# 04_-_Current_Transformers.net
KiCad netlist of a schematic drawn in Altium Designer
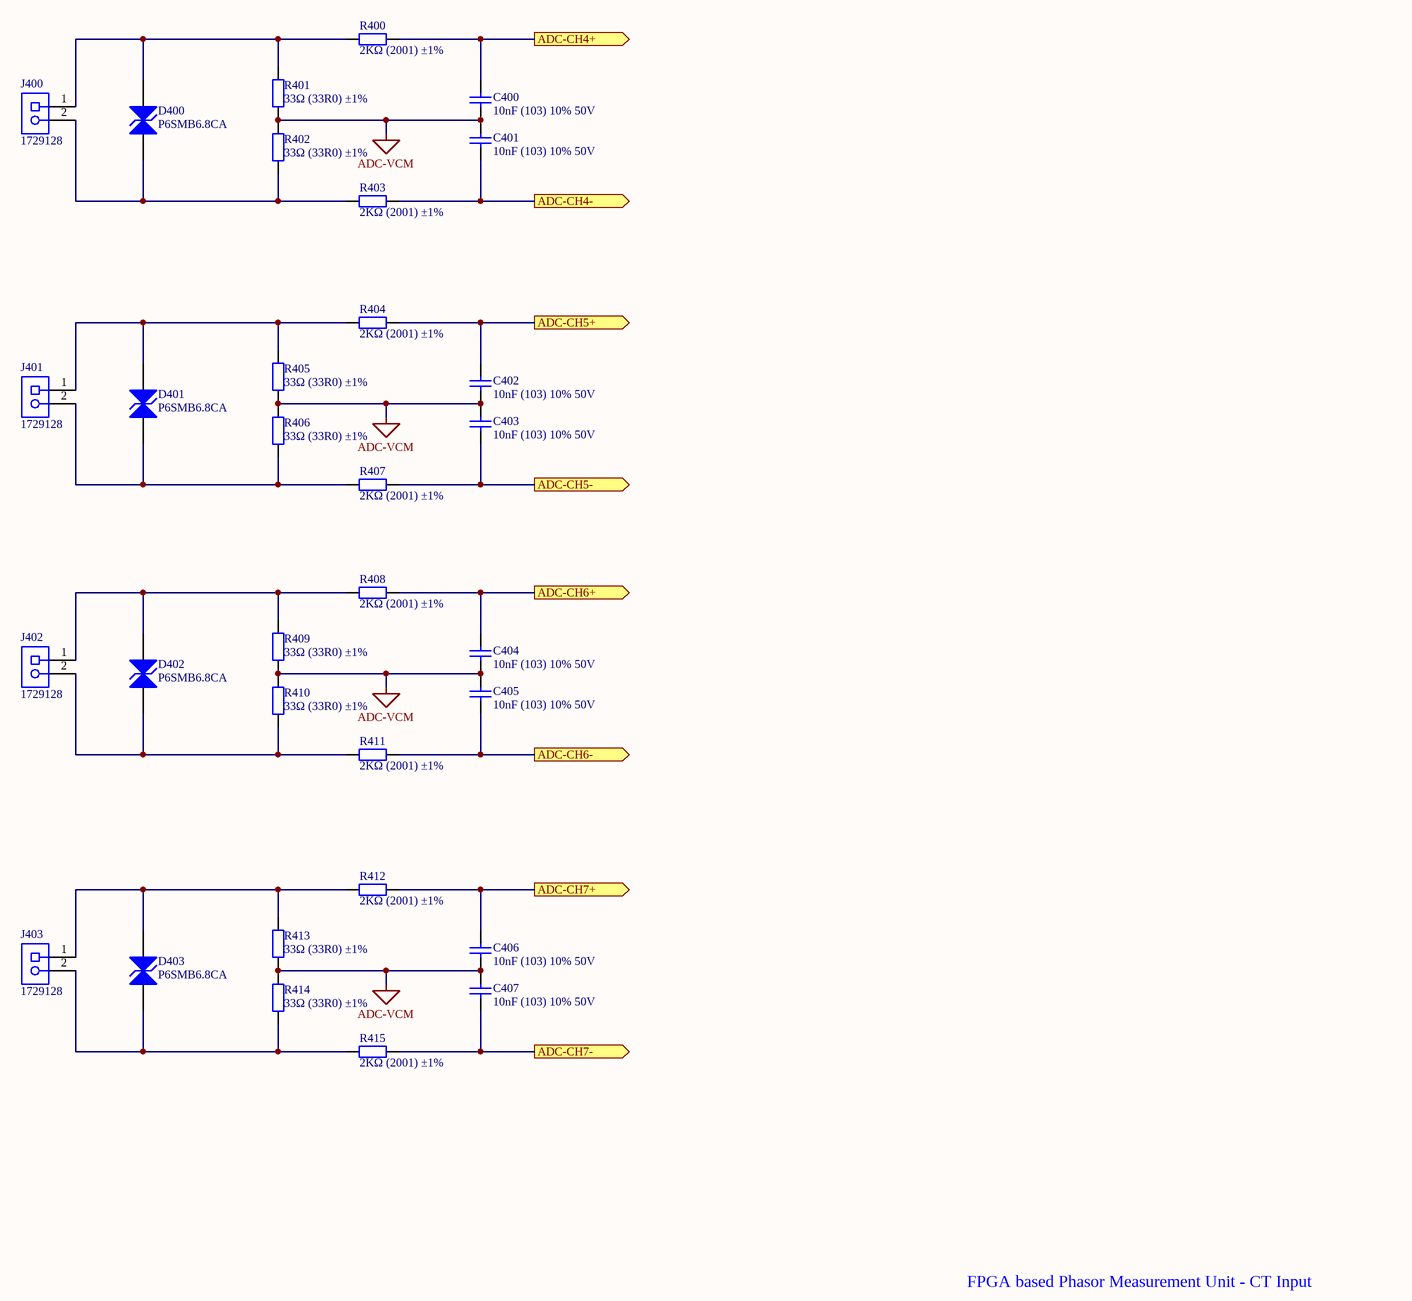
[diagram p0: [04] - Current Transformers.SchDoc]

(export (version "E")
  (design (tool "Eeschema 10.0.6"))
  (components
    (comp (ref "C400")
      (value "10nF (103) 10% 50V")
      (footprint "0805_C")
      (description "贴片电容")
      (libsource (lib "Cap") (part "0805 10nF (103) 10% 50V"))
    )
    (comp (ref "C401")
      (value "10nF (103) 10% 50V")
      (footprint "0805_C")
      (description "贴片电容")
      (libsource (lib "Cap") (part "0805 10nF (103) 10% 50V"))
    )
    (comp (ref "C402")
      (value "10nF (103) 10% 50V")
      (footprint "0805_C")
      (description "贴片电容")
      (libsource (lib "Cap") (part "0805 10nF (103) 10% 50V"))
    )
    (comp (ref "C403")
      (value "10nF (103) 10% 50V")
      (footprint "0805_C")
      (description "贴片电容")
      (libsource (lib "Cap") (part "0805 10nF (103) 10% 50V"))
    )
    (comp (ref "C404")
      (value "10nF (103) 10% 50V")
      (footprint "0805_C")
      (description "贴片电容")
      (libsource (lib "Cap") (part "0805 10nF (103) 10% 50V"))
    )
    (comp (ref "C405")
      (value "10nF (103) 10% 50V")
      (footprint "0805_C")
      (description "贴片电容")
      (libsource (lib "Cap") (part "0805 10nF (103) 10% 50V"))
    )
    (comp (ref "C406")
      (value "10nF (103) 10% 50V")
      (footprint "0805_C")
      (description "贴片电容")
      (libsource (lib "Cap") (part "0805 10nF (103) 10% 50V"))
    )
    (comp (ref "C407")
      (value "10nF (103) 10% 50V")
      (footprint "0805_C")
      (description "贴片电容")
      (libsource (lib "Cap") (part "0805 10nF (103) 10% 50V"))
    )
    (comp (ref "D400")
      (value "P6SMB6.8CA")
      (footprint "SMB(DO-214AA)_S1")
      (description "TVS")
      (libsource (lib "Diode") (part "SMB/DO-214AA P6SMB6.8CA"))
    )
    (comp (ref "D401")
      (value "P6SMB6.8CA")
      (footprint "SMB(DO-214AA)_S1")
      (description "TVS")
      (libsource (lib "Diode") (part "SMB/DO-214AA P6SMB6.8CA"))
    )
    (comp (ref "D402")
      (value "P6SMB6.8CA")
      (footprint "SMB(DO-214AA)_S1")
      (description "TVS")
      (libsource (lib "Diode") (part "SMB/DO-214AA P6SMB6.8CA"))
    )
    (comp (ref "D403")
      (value "P6SMB6.8CA")
      (footprint "SMB(DO-214AA)_S1")
      (description "TVS")
      (libsource (lib "Diode") (part "SMB/DO-214AA P6SMB6.8CA"))
    )
    (comp (ref "J400")
      (value "1729128")
      (footprint "PHOE-1729128-2_V")
      (description "PCB Terminal Block, 13.5 A, 400 V, 2-Pin THD, RoHS, Bulk")
      (fields (field (name "MANUFACTURER") "Phoenix Contact"))
      (libsource (lib "Altium Content Vault") (part "CN-2P-F-R2"))
    )
    (comp (ref "J401")
      (value "1729128")
      (footprint "PHOE-1729128-2_V")
      (description "PCB Terminal Block, 13.5 A, 400 V, 2-Pin THD, RoHS, Bulk")
      (fields (field (name "MANUFACTURER") "Phoenix Contact"))
      (libsource (lib "Altium Content Vault") (part "CN-2P-F-R2"))
    )
    (comp (ref "J402")
      (value "1729128")
      (footprint "PHOE-1729128-2_V")
      (description "PCB Terminal Block, 13.5 A, 400 V, 2-Pin THD, RoHS, Bulk")
      (fields (field (name "MANUFACTURER") "Phoenix Contact"))
      (libsource (lib "Altium Content Vault") (part "CN-2P-F-R2"))
    )
    (comp (ref "J403")
      (value "1729128")
      (footprint "PHOE-1729128-2_V")
      (description "PCB Terminal Block, 13.5 A, 400 V, 2-Pin THD, RoHS, Bulk")
      (fields (field (name "MANUFACTURER") "Phoenix Contact"))
      (libsource (lib "Altium Content Vault") (part "CN-2P-F-R2"))
    )
    (comp (ref "R400")
      (value "2KΩ (2001) ±1%")
      (footprint "0805_R")
      (description "贴片电阻")
      (libsource (lib "RES") (part "0805 2KΩ (2001) 1%"))
    )
    (comp (ref "R401")
      (value "33Ω (33R0) ±1%")
      (footprint "0603_R")
      (description "贴片电阻")
      (libsource (lib "RES") (part "0603 33Ω (33R0) 1%"))
    )
    (comp (ref "R402")
      (value "33Ω (33R0) ±1%")
      (footprint "0603_R")
      (description "贴片电阻")
      (libsource (lib "RES") (part "0603 33Ω (33R0) 1%"))
    )
    (comp (ref "R403")
      (value "2KΩ (2001) ±1%")
      (footprint "0805_R")
      (description "贴片电阻")
      (libsource (lib "RES") (part "0805 2KΩ (2001) 1%"))
    )
    (comp (ref "R404")
      (value "2KΩ (2001) ±1%")
      (footprint "0805_R")
      (description "贴片电阻")
      (libsource (lib "RES") (part "0805 2KΩ (2001) 1%"))
    )
    (comp (ref "R405")
      (value "33Ω (33R0) ±1%")
      (footprint "0603_R")
      (description "贴片电阻")
      (libsource (lib "RES") (part "0603 33Ω (33R0) 1%"))
    )
    (comp (ref "R406")
      (value "33Ω (33R0) ±1%")
      (footprint "0603_R")
      (description "贴片电阻")
      (libsource (lib "RES") (part "0603 33Ω (33R0) 1%"))
    )
    (comp (ref "R407")
      (value "2KΩ (2001) ±1%")
      (footprint "0805_R")
      (description "贴片电阻")
      (libsource (lib "RES") (part "0805 2KΩ (2001) 1%"))
    )
    (comp (ref "R408")
      (value "2KΩ (2001) ±1%")
      (footprint "0805_R")
      (description "贴片电阻")
      (libsource (lib "RES") (part "0805 2KΩ (2001) 1%"))
    )
    (comp (ref "R409")
      (value "33Ω (33R0) ±1%")
      (footprint "0603_R")
      (description "贴片电阻")
      (libsource (lib "RES") (part "0603 33Ω (33R0) 1%"))
    )
    (comp (ref "R410")
      (value "33Ω (33R0) ±1%")
      (footprint "0603_R")
      (description "贴片电阻")
      (libsource (lib "RES") (part "0603 33Ω (33R0) 1%"))
    )
    (comp (ref "R411")
      (value "2KΩ (2001) ±1%")
      (footprint "0805_R")
      (description "贴片电阻")
      (libsource (lib "RES") (part "0805 2KΩ (2001) 1%"))
    )
    (comp (ref "R412")
      (value "2KΩ (2001) ±1%")
      (footprint "0805_R")
      (description "贴片电阻")
      (libsource (lib "RES") (part "0805 2KΩ (2001) 1%"))
    )
    (comp (ref "R413")
      (value "33Ω (33R0) ±1%")
      (footprint "0603_R")
      (description "贴片电阻")
      (libsource (lib "RES") (part "0603 33Ω (33R0) 1%"))
    )
    (comp (ref "R414")
      (value "33Ω (33R0) ±1%")
      (footprint "0603_R")
      (description "贴片电阻")
      (libsource (lib "RES") (part "0603 33Ω (33R0) 1%"))
    )
    (comp (ref "R415")
      (value "2KΩ (2001) ±1%")
      (footprint "0805_R")
      (description "贴片电阻")
      (libsource (lib "RES") (part "0805 2KΩ (2001) 1%"))
    )
  )
  (nets
    (net (code "1") (name "/ADC-CH4+") (class "Default")
      (node (ref "C400") (pin "2") (pinfunction "2_2") (pintype "passive"))
      (node (ref "R400") (pin "1") (pinfunction "1_1") (pintype "passive"))
    )
    (net (code "2") (name "/ADC-CH4-") (class "Default")
      (node (ref "C401") (pin "1") (pinfunction "1_1") (pintype "passive"))
      (node (ref "R403") (pin "1") (pinfunction "1_1") (pintype "passive"))
    )
    (net (code "3") (name "/ADC-CH5+") (class "Default")
      (node (ref "C402") (pin "2") (pinfunction "2_2") (pintype "passive"))
      (node (ref "R404") (pin "1") (pinfunction "1_1") (pintype "passive"))
    )
    (net (code "4") (name "/ADC-CH5-") (class "Default")
      (node (ref "C403") (pin "1") (pinfunction "1_1") (pintype "passive"))
      (node (ref "R407") (pin "1") (pinfunction "1_1") (pintype "passive"))
    )
    (net (code "5") (name "/ADC-CH6+") (class "Default")
      (node (ref "C404") (pin "2") (pinfunction "2_2") (pintype "passive"))
      (node (ref "R408") (pin "1") (pinfunction "1_1") (pintype "passive"))
    )
    (net (code "6") (name "/ADC-CH6-") (class "Default")
      (node (ref "C405") (pin "1") (pinfunction "1_1") (pintype "passive"))
      (node (ref "R411") (pin "1") (pinfunction "1_1") (pintype "passive"))
    )
    (net (code "7") (name "/ADC-CH7+") (class "Default")
      (node (ref "C406") (pin "2") (pinfunction "2_2") (pintype "passive"))
      (node (ref "R412") (pin "1") (pinfunction "1_1") (pintype "passive"))
    )
    (net (code "8") (name "/ADC-CH7-") (class "Default")
      (node (ref "C407") (pin "1") (pinfunction "1_1") (pintype "passive"))
      (node (ref "R415") (pin "1") (pinfunction "1_1") (pintype "passive"))
    )
    (net (code "9") (name "ADC-VCM") (class "Default")
      (node (ref "C400") (pin "1") (pinfunction "1_1") (pintype "passive"))
      (node (ref "C401") (pin "2") (pinfunction "2_2") (pintype "passive"))
      (node (ref "C402") (pin "1") (pinfunction "1_1") (pintype "passive"))
      (node (ref "C403") (pin "2") (pinfunction "2_2") (pintype "passive"))
      (node (ref "C404") (pin "1") (pinfunction "1_1") (pintype "passive"))
      (node (ref "C405") (pin "2") (pinfunction "2_2") (pintype "passive"))
      (node (ref "C406") (pin "1") (pinfunction "1_1") (pintype "passive"))
      (node (ref "C407") (pin "2") (pinfunction "2_2") (pintype "passive"))
      (node (ref "R401") (pin "1") (pinfunction "1_1") (pintype "passive"))
      (node (ref "R402") (pin "2") (pinfunction "2_2") (pintype "passive"))
      (node (ref "R405") (pin "1") (pinfunction "1_1") (pintype "passive"))
      (node (ref "R406") (pin "2") (pinfunction "2_2") (pintype "passive"))
      (node (ref "R409") (pin "1") (pinfunction "1_1") (pintype "passive"))
      (node (ref "R410") (pin "2") (pinfunction "2_2") (pintype "passive"))
      (node (ref "R413") (pin "1") (pinfunction "1_1") (pintype "passive"))
      (node (ref "R414") (pin "2") (pinfunction "2_2") (pintype "passive"))
    )
    (net (code "10") (name "Net-(D400-A)") (class "Default")
      (node (ref "D400") (pin "1") (pinfunction "A_1") (pintype "passive"))
      (node (ref "J400") (pin "2") (pinfunction "2_2") (pintype "passive"))
      (node (ref "R402") (pin "1") (pinfunction "1_1") (pintype "passive"))
      (node (ref "R403") (pin "2") (pinfunction "2_2") (pintype "passive"))
    )
    (net (code "11") (name "Net-(D400-K)") (class "Default")
      (node (ref "D400") (pin "2") (pinfunction "K_2") (pintype "passive"))
      (node (ref "J400") (pin "1") (pinfunction "1_1") (pintype "passive"))
      (node (ref "R400") (pin "2") (pinfunction "2_2") (pintype "passive"))
      (node (ref "R401") (pin "2") (pinfunction "2_2") (pintype "passive"))
    )
    (net (code "12") (name "Net-(D401-A)") (class "Default")
      (node (ref "D401") (pin "1") (pinfunction "A_1") (pintype "passive"))
      (node (ref "J401") (pin "2") (pinfunction "2_2") (pintype "passive"))
      (node (ref "R406") (pin "1") (pinfunction "1_1") (pintype "passive"))
      (node (ref "R407") (pin "2") (pinfunction "2_2") (pintype "passive"))
    )
    (net (code "13") (name "Net-(D401-K)") (class "Default")
      (node (ref "D401") (pin "2") (pinfunction "K_2") (pintype "passive"))
      (node (ref "J401") (pin "1") (pinfunction "1_1") (pintype "passive"))
      (node (ref "R404") (pin "2") (pinfunction "2_2") (pintype "passive"))
      (node (ref "R405") (pin "2") (pinfunction "2_2") (pintype "passive"))
    )
    (net (code "14") (name "Net-(D402-A)") (class "Default")
      (node (ref "D402") (pin "1") (pinfunction "A_1") (pintype "passive"))
      (node (ref "J402") (pin "2") (pinfunction "2_2") (pintype "passive"))
      (node (ref "R410") (pin "1") (pinfunction "1_1") (pintype "passive"))
      (node (ref "R411") (pin "2") (pinfunction "2_2") (pintype "passive"))
    )
    (net (code "15") (name "Net-(D402-K)") (class "Default")
      (node (ref "D402") (pin "2") (pinfunction "K_2") (pintype "passive"))
      (node (ref "J402") (pin "1") (pinfunction "1_1") (pintype "passive"))
      (node (ref "R408") (pin "2") (pinfunction "2_2") (pintype "passive"))
      (node (ref "R409") (pin "2") (pinfunction "2_2") (pintype "passive"))
    )
    (net (code "16") (name "Net-(D403-A)") (class "Default")
      (node (ref "D403") (pin "1") (pinfunction "A_1") (pintype "passive"))
      (node (ref "J403") (pin "2") (pinfunction "2_2") (pintype "passive"))
      (node (ref "R414") (pin "1") (pinfunction "1_1") (pintype "passive"))
      (node (ref "R415") (pin "2") (pinfunction "2_2") (pintype "passive"))
    )
    (net (code "17") (name "Net-(D403-K)") (class "Default")
      (node (ref "D403") (pin "2") (pinfunction "K_2") (pintype "passive"))
      (node (ref "J403") (pin "1") (pinfunction "1_1") (pintype "passive"))
      (node (ref "R412") (pin "2") (pinfunction "2_2") (pintype "passive"))
      (node (ref "R413") (pin "2") (pinfunction "2_2") (pintype "passive"))
    )
  )
)
